# TIMER_COUNTER_PANEL.net
KiCad netlist of a schematic drawn in Altium Designer
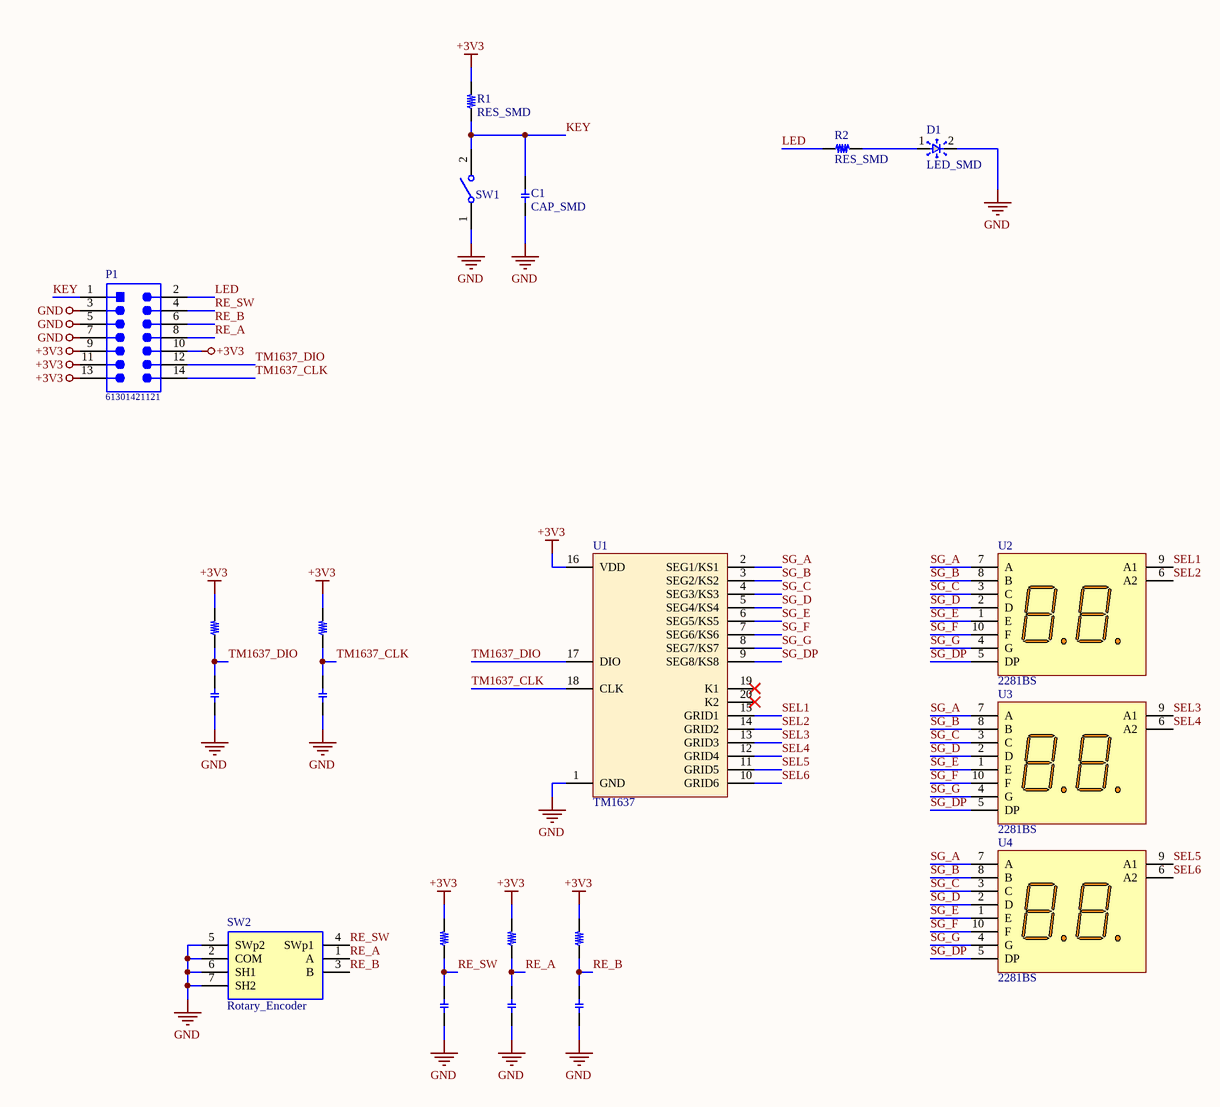
[diagram p0: TIMER_COUNTER_PANEL.SchDoc]

(export (version "E")
  (design (tool "Eeschema 10.0.6"))
  (components
    (comp (ref "C1")
      (value "CAP_SMD")
      (footprint "C 0603")
      (libsource (lib "radmehr_library") (part "CAP_SMD"))
    )
    (comp (ref "C2")
      (value "CAP_SMD")
      (footprint "C 0603")
      (libsource (lib "radmehr_library") (part "CAP_SMD"))
    )
    (comp (ref "C3")
      (value "CAP_SMD")
      (footprint "C 0603")
      (libsource (lib "radmehr_library") (part "CAP_SMD"))
    )
    (comp (ref "C4")
      (value "CAP_SMD")
      (footprint "C 0603")
      (libsource (lib "radmehr_library") (part "CAP_SMD"))
    )
    (comp (ref "C5")
      (value "CAP_SMD")
      (footprint "C 0603")
      (libsource (lib "radmehr_library") (part "CAP_SMD"))
    )
    (comp (ref "C6")
      (value "CAP_SMD")
      (footprint "C 0603")
      (libsource (lib "radmehr_library") (part "CAP_SMD"))
    )
    (comp (ref "D1")
      (value "LED_SMD")
      (footprint "D 0603")
      (libsource (lib "radmehr_library") (part "LED_SMD"))
    )
    (comp (ref "P1")
      (value "61301421121")
      (footprint "61301421121")
      (description "WR-PHD Pin Header, THT, pitch 2.54mm, Dual Row, Vertical, 14p")
      (fields (field (name "MANUFACTURER") "Wurth Elektronik"))
      (libsource (lib "Altium_WR-PHD (rev22a)") (part "61301421121"))
    )
    (comp (ref "R1")
      (value "RES_SMD")
      (footprint "R 0603")
      (libsource (lib "radmehr_library") (part "RES_SMD"))
    )
    (comp (ref "R2")
      (value "RES_SMD")
      (footprint "R 0603")
      (libsource (lib "radmehr_library") (part "RES_SMD"))
    )
    (comp (ref "R3")
      (value "RES_SMD")
      (footprint "R 0603")
      (libsource (lib "radmehr_library") (part "RES_SMD"))
    )
    (comp (ref "R4")
      (value "RES_SMD")
      (footprint "R 0603")
      (libsource (lib "radmehr_library") (part "RES_SMD"))
    )
    (comp (ref "R5")
      (value "RES_SMD")
      (footprint "R 0603")
      (libsource (lib "radmehr_library") (part "RES_SMD"))
    )
    (comp (ref "R6")
      (value "RES_SMD")
      (footprint "R 0603")
      (libsource (lib "radmehr_library") (part "RES_SMD"))
    )
    (comp (ref "R7")
      (value "RES_SMD")
      (footprint "R 0603")
      (libsource (lib "radmehr_library") (part "RES_SMD"))
    )
    (comp (ref "SW1")
      (value "430133050816")
      (footprint "WS-TASV_L6W6H5_4301330508x6")
      (description "WS-TASV SMT long travel tact switch, L6 x W6 x H5mm, 160g, SPST-NO, 16V, 50mA")
      (fields (field (name "MANUFACTURER") "Wurth Elektronik"))
      (libsource (lib "Altium_WS-TASV (rev22c) (1)") (part "430133050816"))
    )
    (comp (ref "SW2")
      (value "Rotary_Encoder")
      (footprint "Rotary_Encoder")
      (libsource (lib "radmehr_library") (part "Rotary_Encoder"))
    )
    (comp (ref "U1")
      (value "TM1637")
      (footprint "SOP-20")
      (libsource (lib "radmehr_library") (part "TM1637"))
    )
    (comp (ref "U2")
      (value "2281BS")
      (footprint "2281BS")
      (libsource (lib "radmehr_library") (part "2281BS"))
    )
    (comp (ref "U3")
      (value "2281BS")
      (footprint "2281BS")
      (libsource (lib "radmehr_library") (part "2281BS"))
    )
    (comp (ref "U4")
      (value "2281BS")
      (footprint "2281BS")
      (libsource (lib "radmehr_library") (part "2281BS"))
    )
  )
  (nets
    (net (code "1") (name "+3V3") (class "Default")
      (node (ref "P1") (pin "10") (pinfunction "10_10") (pintype "passive"))
      (node (ref "P1") (pin "11") (pinfunction "11_11") (pintype "passive"))
      (node (ref "P1") (pin "13") (pinfunction "13_13") (pintype "passive"))
      (node (ref "P1") (pin "9") (pinfunction "9_9") (pintype "passive"))
      (node (ref "R1") (pin "2") (pinfunction "2_2") (pintype "passive"))
      (node (ref "R3") (pin "2") (pinfunction "2_2") (pintype "passive"))
      (node (ref "R4") (pin "2") (pinfunction "2_2") (pintype "passive"))
      (node (ref "R5") (pin "2") (pinfunction "2_2") (pintype "passive"))
      (node (ref "R6") (pin "2") (pinfunction "2_2") (pintype "passive"))
      (node (ref "R7") (pin "2") (pinfunction "2_2") (pintype "passive"))
      (node (ref "U1") (pin "16") (pinfunction "VDD_16") (pintype "passive"))
    )
    (net (code "2") (name "/KEY") (class "Default")
      (node (ref "C1") (pin "2") (pinfunction "2_2") (pintype "passive"))
      (node (ref "P1") (pin "1") (pinfunction "1_1") (pintype "passive"))
      (node (ref "R1") (pin "1") (pinfunction "1_1") (pintype "passive"))
      (node (ref "SW1") (pin "2") (pinfunction "2_2") (pintype "passive"))
    )
    (net (code "3") (name "/LED") (class "Default")
      (node (ref "P1") (pin "2") (pinfunction "2_2") (pintype "passive"))
      (node (ref "R2") (pin "1") (pinfunction "1_1") (pintype "passive"))
    )
    (net (code "4") (name "/RE_A") (class "Default")
      (node (ref "C5") (pin "2") (pinfunction "2_2") (pintype "passive"))
      (node (ref "P1") (pin "8") (pinfunction "8_8") (pintype "passive"))
      (node (ref "R6") (pin "1") (pinfunction "1_1") (pintype "passive"))
      (node (ref "SW2") (pin "1") (pinfunction "A_1") (pintype "passive"))
    )
    (net (code "5") (name "/RE_B") (class "Default")
      (node (ref "C6") (pin "2") (pinfunction "2_2") (pintype "passive"))
      (node (ref "P1") (pin "6") (pinfunction "6_6") (pintype "passive"))
      (node (ref "R7") (pin "1") (pinfunction "1_1") (pintype "passive"))
      (node (ref "SW2") (pin "3") (pinfunction "B_3") (pintype "passive"))
    )
    (net (code "6") (name "/RE_SW") (class "Default")
      (node (ref "C4") (pin "2") (pinfunction "2_2") (pintype "passive"))
      (node (ref "P1") (pin "4") (pinfunction "4_4") (pintype "passive"))
      (node (ref "R5") (pin "1") (pinfunction "1_1") (pintype "passive"))
      (node (ref "SW2") (pin "4") (pinfunction "SWp1_4") (pintype "passive"))
    )
    (net (code "7") (name "/SEL1") (class "Default")
      (node (ref "U1") (pin "15") (pinfunction "GRID1_15") (pintype "passive"))
      (node (ref "U2") (pin "9") (pinfunction "A1_9") (pintype "passive"))
    )
    (net (code "8") (name "/SEL2") (class "Default")
      (node (ref "U1") (pin "14") (pinfunction "GRID2_14") (pintype "passive"))
      (node (ref "U2") (pin "6") (pinfunction "A2_6") (pintype "passive"))
    )
    (net (code "9") (name "/SEL3") (class "Default")
      (node (ref "U1") (pin "13") (pinfunction "GRID3_13") (pintype "passive"))
      (node (ref "U3") (pin "9") (pinfunction "A1_9") (pintype "passive"))
    )
    (net (code "10") (name "/SEL4") (class "Default")
      (node (ref "U1") (pin "12") (pinfunction "GRID4_12") (pintype "passive"))
      (node (ref "U3") (pin "6") (pinfunction "A2_6") (pintype "passive"))
    )
    (net (code "11") (name "/SEL5") (class "Default")
      (node (ref "U1") (pin "11") (pinfunction "GRID5_11") (pintype "passive"))
      (node (ref "U4") (pin "9") (pinfunction "A1_9") (pintype "passive"))
    )
    (net (code "12") (name "/SEL6") (class "Default")
      (node (ref "U1") (pin "10") (pinfunction "GRID6_10") (pintype "passive"))
      (node (ref "U4") (pin "6") (pinfunction "A2_6") (pintype "passive"))
    )
    (net (code "13") (name "/SG_A") (class "Default")
      (node (ref "U1") (pin "2") (pinfunction "SEG1/KS1_2") (pintype "passive"))
      (node (ref "U2") (pin "7") (pinfunction "A_7") (pintype "passive"))
      (node (ref "U3") (pin "7") (pinfunction "A_7") (pintype "passive"))
      (node (ref "U4") (pin "7") (pinfunction "A_7") (pintype "passive"))
    )
    (net (code "14") (name "/SG_B") (class "Default")
      (node (ref "U1") (pin "3") (pinfunction "SEG2/KS2_3") (pintype "passive"))
      (node (ref "U2") (pin "8") (pinfunction "B_8") (pintype "passive"))
      (node (ref "U3") (pin "8") (pinfunction "B_8") (pintype "passive"))
      (node (ref "U4") (pin "8") (pinfunction "B_8") (pintype "passive"))
    )
    (net (code "15") (name "/SG_C") (class "Default")
      (node (ref "U1") (pin "4") (pinfunction "SEG3/KS3_4") (pintype "passive"))
      (node (ref "U2") (pin "3") (pinfunction "C_3") (pintype "passive"))
      (node (ref "U3") (pin "3") (pinfunction "C_3") (pintype "passive"))
      (node (ref "U4") (pin "3") (pinfunction "C_3") (pintype "passive"))
    )
    (net (code "16") (name "/SG_D") (class "Default")
      (node (ref "U1") (pin "5") (pinfunction "SEG4/KS4_5") (pintype "passive"))
      (node (ref "U2") (pin "2") (pinfunction "D_2") (pintype "passive"))
      (node (ref "U3") (pin "2") (pinfunction "D_2") (pintype "passive"))
      (node (ref "U4") (pin "2") (pinfunction "D_2") (pintype "passive"))
    )
    (net (code "17") (name "/SG_DP") (class "Default")
      (node (ref "U1") (pin "9") (pinfunction "SEG8/KS8_9") (pintype "passive"))
      (node (ref "U2") (pin "5") (pinfunction "DP_5") (pintype "passive"))
      (node (ref "U3") (pin "5") (pinfunction "DP_5") (pintype "passive"))
      (node (ref "U4") (pin "5") (pinfunction "DP_5") (pintype "passive"))
    )
    (net (code "18") (name "/SG_E") (class "Default")
      (node (ref "U1") (pin "6") (pinfunction "SEG5/KS5_6") (pintype "passive"))
      (node (ref "U2") (pin "1") (pinfunction "E_1") (pintype "passive"))
      (node (ref "U3") (pin "1") (pinfunction "E_1") (pintype "passive"))
      (node (ref "U4") (pin "1") (pinfunction "E_1") (pintype "passive"))
    )
    (net (code "19") (name "/SG_F") (class "Default")
      (node (ref "U1") (pin "7") (pinfunction "SEG6/KS6_7") (pintype "passive"))
      (node (ref "U2") (pin "10") (pinfunction "F_10") (pintype "passive"))
      (node (ref "U3") (pin "10") (pinfunction "F_10") (pintype "passive"))
      (node (ref "U4") (pin "10") (pinfunction "F_10") (pintype "passive"))
    )
    (net (code "20") (name "/SG_G") (class "Default")
      (node (ref "U1") (pin "8") (pinfunction "SEG7/KS7_8") (pintype "passive"))
      (node (ref "U2") (pin "4") (pinfunction "G_4") (pintype "passive"))
      (node (ref "U3") (pin "4") (pinfunction "G_4") (pintype "passive"))
      (node (ref "U4") (pin "4") (pinfunction "G_4") (pintype "passive"))
    )
    (net (code "21") (name "/TM1637_CLK") (class "Default")
      (node (ref "C3") (pin "2") (pinfunction "2_2") (pintype "passive"))
      (node (ref "P1") (pin "14") (pinfunction "14_14") (pintype "passive"))
      (node (ref "R4") (pin "1") (pinfunction "1_1") (pintype "passive"))
      (node (ref "U1") (pin "18") (pinfunction "CLK_18") (pintype "passive"))
    )
    (net (code "22") (name "/TM1637_DIO") (class "Default")
      (node (ref "C2") (pin "2") (pinfunction "2_2") (pintype "passive"))
      (node (ref "P1") (pin "12") (pinfunction "12_12") (pintype "passive"))
      (node (ref "R3") (pin "1") (pinfunction "1_1") (pintype "passive"))
      (node (ref "U1") (pin "17") (pinfunction "DIO_17") (pintype "passive"))
    )
    (net (code "23") (name "GND") (class "Default")
      (node (ref "C1") (pin "1") (pinfunction "1_1") (pintype "passive"))
      (node (ref "C2") (pin "1") (pinfunction "1_1") (pintype "passive"))
      (node (ref "C3") (pin "1") (pinfunction "1_1") (pintype "passive"))
      (node (ref "C4") (pin "1") (pinfunction "1_1") (pintype "passive"))
      (node (ref "C5") (pin "1") (pinfunction "1_1") (pintype "passive"))
      (node (ref "C6") (pin "1") (pinfunction "1_1") (pintype "passive"))
      (node (ref "D1") (pin "2") (pintype "passive"))
      (node (ref "P1") (pin "3") (pinfunction "3_3") (pintype "passive"))
      (node (ref "P1") (pin "5") (pinfunction "5_5") (pintype "passive"))
      (node (ref "P1") (pin "7") (pinfunction "7_7") (pintype "passive"))
      (node (ref "SW1") (pin "1") (pinfunction "1_1") (pintype "passive"))
      (node (ref "SW2") (pin "2") (pinfunction "COM_2") (pintype "passive"))
      (node (ref "SW2") (pin "5") (pinfunction "SWp2_5") (pintype "passive"))
      (node (ref "SW2") (pin "6") (pinfunction "SH1_6") (pintype "passive"))
      (node (ref "SW2") (pin "7") (pinfunction "SH2_7") (pintype "passive"))
      (node (ref "U1") (pin "1") (pinfunction "GND_1") (pintype "passive"))
    )
    (net (code "24") (name "Net-(D1-Pad1)") (class "Default")
      (node (ref "D1") (pin "1") (pintype "passive"))
      (node (ref "R2") (pin "2") (pinfunction "2_2") (pintype "passive"))
    )
    (net (code "25") (name "unconnected-(U1-K1-Pad19)") (class "Default")
      (node (ref "U1") (pin "19") (pinfunction "K1_19") (pintype "passive+no_connect"))
    )
    (net (code "26") (name "unconnected-(U1-K2-Pad20)") (class "Default")
      (node (ref "U1") (pin "20") (pinfunction "K2_20") (pintype "passive+no_connect"))
    )
  )
)
